# Rauchmelder_2_2.net
KiCad netlist of a schematic drawn in EAGLE
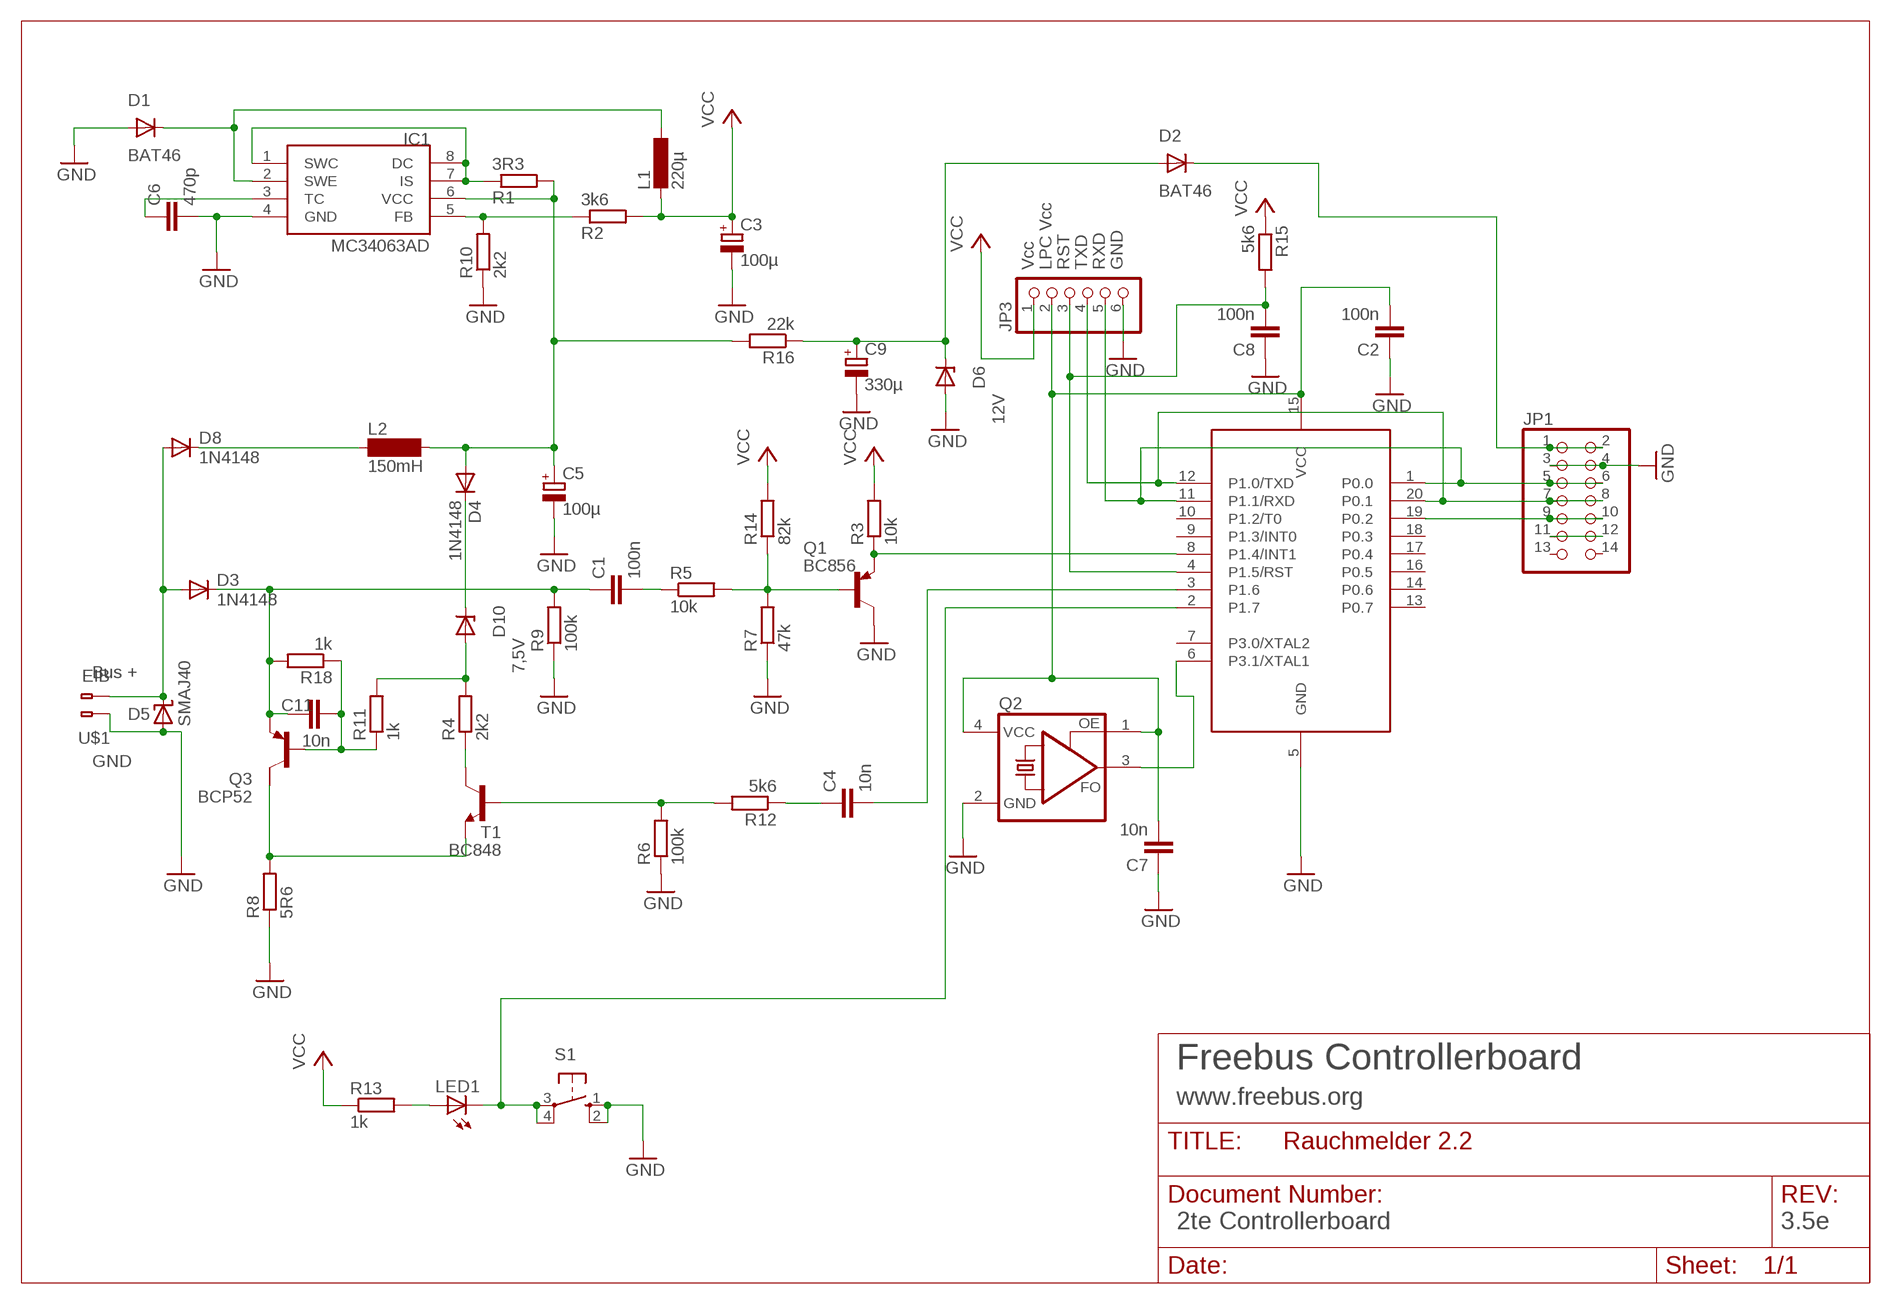
[diagram p0: schematic, sheet 1]

(export (version "E")
  (design (tool "Eeschema 10.0.6"))
  (components
    (comp (ref "C1")
      (value "100n")
      (footprint "eagle-import:C1206")
      (libsource (lib "eagle-import") (part "C-EUC1206"))
    )
    (comp (ref "C2")
      (value "100n")
      (footprint "eagle-import:C1206")
      (libsource (lib "eagle-import") (part "C-EUC1206"))
    )
    (comp (ref "C3")
      (value "100µ")
      (footprint "eagle-import:SANYO-OSCON_SMD_B6")
      (libsource (lib "eagle-import") (part "CPOL-EUSANYO_SMD_B6"))
    )
    (comp (ref "C4")
      (value "10n")
      (footprint "eagle-import:C1206")
      (libsource (lib "eagle-import") (part "C-EUC1206"))
    )
    (comp (ref "C5")
      (value "100µ")
      (footprint "eagle-import:SANYO-OSCON_SMD_C6")
      (libsource (lib "eagle-import") (part "CPOL-EUSANYO_SMD_C6"))
    )
    (comp (ref "C6")
      (value "470p")
      (footprint "eagle-import:C1206")
      (libsource (lib "eagle-import") (part "C-EUC1206"))
    )
    (comp (ref "C7")
      (value "10n")
      (footprint "eagle-import:C1206")
      (libsource (lib "eagle-import") (part "C-EUC1206"))
    )
    (comp (ref "C8")
      (value "100n")
      (footprint "eagle-import:C1206")
      (libsource (lib "eagle-import") (part "C-EUC1206"))
    )
    (comp (ref "C9")
      (value "330µ")
      (footprint "eagle-import:E3,5-8")
      (libsource (lib "eagle-import") (part "CPOL-EUE3.5-8"))
    )
    (comp (ref "C11")
      (value "10n")
      (footprint "eagle-import:C1206")
      (libsource (lib "eagle-import") (part "C-EUC1206"))
    )
    (comp (ref "D1")
      (value "BAT46")
      (footprint "eagle-import:MINIMELF")
      (libsource (lib "eagle-import") (part "DIODE-MINIMELF"))
    )
    (comp (ref "D2")
      (value "BAT46")
      (footprint "eagle-import:MINIMELF")
      (libsource (lib "eagle-import") (part "DIODE-MINIMELF"))
    )
    (comp (ref "D3")
      (value "1N4148")
      (footprint "eagle-import:MINIMELF")
      (libsource (lib "eagle-import") (part "DIODE-MINIMELF"))
    )
    (comp (ref "D4")
      (value "1N4148")
      (footprint "eagle-import:MINIMELF")
      (libsource (lib "eagle-import") (part "DIODE-MINIMELF"))
    )
    (comp (ref "D5")
      (value "SMAJ40")
      (footprint "eagle-import:SMBJ")
      (libsource (lib "eagle-import") (part "SUPPRESSOR-SMBJ"))
    )
    (comp (ref "D6")
      (value "12V")
      (footprint "eagle-import:MINIMELF")
      (libsource (lib "eagle-import") (part "ZPD"))
    )
    (comp (ref "D8")
      (value "1N4148")
      (footprint "eagle-import:MINIMELF")
      (libsource (lib "eagle-import") (part "DIODE-MINIMELF"))
    )
    (comp (ref "D10")
      (value "7,5V")
      (footprint "eagle-import:MINIMELF")
      (libsource (lib "eagle-import") (part "ZPD"))
    )
    (comp (ref "IC1")
      (value "MC34063AD")
      (footprint "eagle-import:SOIC8")
      (libsource (lib "eagle-import") (part "MC34063AD"))
    )
    (comp (ref "IC3")
      (value "LPC922FDH")
      (footprint "eagle-import:TSSOP20")
      (libsource (lib "eagle-import") (part "LPC922FDH"))
    )
    (comp (ref "JP1")
      (value "PINHD-2X7")
      (footprint "eagle-import:2X07")
      (libsource (lib "eagle-import") (part "PINHD-2X7"))
    )
    (comp (ref "JP3")
      (value "PINHD-1X6")
      (footprint "eagle-import:1X06")
      (libsource (lib "eagle-import") (part "PINHD-1X6"))
    )
    (comp (ref "L1")
      (value "220µ")
      (footprint "eagle-import:0207_12")
      (libsource (lib "eagle-import") (part "L-EU0207/12"))
    )
    (comp (ref "L2")
      (value "150mH")
      (footprint "eagle-import:BS11")
      (libsource (lib "eagle-import") (part "BS11"))
    )
    (comp (ref "LED1")
      (value "LED3MM")
      (footprint "eagle-import:LED3MM")
      (libsource (lib "eagle-import") (part "LED3MM"))
    )
    (comp (ref "Q1")
      (value "BC856")
      (footprint "eagle-import:SOT23-BEC")
      (libsource (lib "eagle-import") (part "BC856SMDALT1"))
    )
    (comp (ref "Q2")
      (value "ASFL")
      (footprint "eagle-import:ASF")
      (libsource (lib "eagle-import") (part "ASFL"))
    )
    (comp (ref "Q3")
      (value "BCP52")
      (footprint "eagle-import:SOT223")
      (libsource (lib "eagle-import") (part "FZT753SMD"))
    )
    (comp (ref "R1")
      (value "3R3")
      (footprint "eagle-import:R1206")
      (libsource (lib "eagle-import") (part "R-EU_R1206"))
    )
    (comp (ref "R2")
      (value "3k6")
      (footprint "eagle-import:R1206")
      (libsource (lib "eagle-import") (part "R-EU_R1206"))
    )
    (comp (ref "R3")
      (value "10k")
      (footprint "eagle-import:R1206")
      (libsource (lib "eagle-import") (part "R-EU_R1206"))
    )
    (comp (ref "R4")
      (value "2k2")
      (footprint "eagle-import:R1206")
      (libsource (lib "eagle-import") (part "R-EU_R1206"))
    )
    (comp (ref "R5")
      (value "10k")
      (footprint "eagle-import:R1206")
      (libsource (lib "eagle-import") (part "R-EU_R1206"))
    )
    (comp (ref "R6")
      (value "100k")
      (footprint "eagle-import:R1206")
      (libsource (lib "eagle-import") (part "R-EU_R1206"))
    )
    (comp (ref "R7")
      (value "47k")
      (footprint "eagle-import:R1206")
      (libsource (lib "eagle-import") (part "R-EU_R1206"))
    )
    (comp (ref "R8")
      (value "5R6")
      (footprint "eagle-import:R1206")
      (libsource (lib "eagle-import") (part "R-EU_R1206"))
    )
    (comp (ref "R9")
      (value "100k")
      (footprint "eagle-import:R1206")
      (libsource (lib "eagle-import") (part "R-EU_R1206"))
    )
    (comp (ref "R10")
      (value "2k2")
      (footprint "eagle-import:R1206")
      (libsource (lib "eagle-import") (part "R-EU_R1206"))
    )
    (comp (ref "R11")
      (value "1k")
      (footprint "eagle-import:R1206")
      (libsource (lib "eagle-import") (part "R-EU_R1206"))
    )
    (comp (ref "R12")
      (value "5k6")
      (footprint "eagle-import:R1206")
      (libsource (lib "eagle-import") (part "R-EU_R1206"))
    )
    (comp (ref "R13")
      (value "1k")
      (footprint "eagle-import:R1206")
      (libsource (lib "eagle-import") (part "R-EU_R1206"))
    )
    (comp (ref "R14")
      (value "82k")
      (footprint "eagle-import:R1206")
      (libsource (lib "eagle-import") (part "R-EU_R1206"))
    )
    (comp (ref "R15")
      (value "5k6")
      (footprint "eagle-import:R1206")
      (libsource (lib "eagle-import") (part "R-EU_R1206"))
    )
    (comp (ref "R16")
      (value "22k")
      (footprint "eagle-import:R1206")
      (libsource (lib "eagle-import") (part "R-EU_R1206"))
    )
    (comp (ref "R18")
      (value "1k")
      (footprint "eagle-import:R1206")
      (libsource (lib "eagle-import") (part "R-EU_R1206"))
    )
    (comp (ref "S1")
      (value "10-XX")
      (footprint "eagle-import:B3F-10XX")
      (libsource (lib "eagle-import") (part "10-XX"))
    )
    (comp (ref "T1")
      (value "BC848")
      (footprint "eagle-import:SOT23")
      (libsource (lib "eagle-import") (part "BC848"))
    )
    (comp (ref "U$1")
      (value "EIB")
      (footprint "eagle-import:BUSKLEMME243-724")
      (libsource (lib "eagle-import") (part "EIB"))
    )
  )
  (nets
    (net (code "1") (name "GND") (class "Default")
      (node (ref "C2") (pin "1") (pinfunction "1_1") (pintype "passive"))
      (node (ref "C3") (pin "-") (pinfunction "-_-") (pintype "passive"))
      (node (ref "C5") (pin "-") (pinfunction "-_-") (pintype "passive"))
      (node (ref "C6") (pin "2") (pinfunction "2_2") (pintype "passive"))
      (node (ref "C7") (pin "1") (pinfunction "1_1") (pintype "passive"))
      (node (ref "C8") (pin "1") (pinfunction "1_1") (pintype "passive"))
      (node (ref "C9") (pin "-") (pinfunction "-_-") (pintype "passive"))
      (node (ref "D1") (pin "A") (pinfunction "A_A") (pintype "passive"))
      (node (ref "D5") (pin "A") (pinfunction "A_A") (pintype "passive"))
      (node (ref "D6") (pin "A") (pinfunction "A_A") (pintype "passive"))
      (node (ref "IC1") (pin "4") (pinfunction "GND_4") (pintype "passive"))
      (node (ref "IC3") (pin "5") (pinfunction "GND_5") (pintype "bidirectional"))
      (node (ref "JP1") (pin "3") (pinfunction "3_3") (pintype "passive"))
      (node (ref "JP1") (pin "4") (pinfunction "4_4") (pintype "passive"))
      (node (ref "JP3") (pin "6") (pinfunction "6_6") (pintype "passive"))
      (node (ref "Q1") (pin "C") (pinfunction "C_C") (pintype "passive"))
      (node (ref "Q2") (pin "2") (pinfunction "GND_2") (pintype "power_in"))
      (node (ref "R10") (pin "1") (pinfunction "1_1") (pintype "passive"))
      (node (ref "R6") (pin "1") (pinfunction "1_1") (pintype "passive"))
      (node (ref "R7") (pin "1") (pinfunction "1_1") (pintype "passive"))
      (node (ref "R8") (pin "1") (pinfunction "1_1") (pintype "passive"))
      (node (ref "R9") (pin "1") (pinfunction "1_1") (pintype "passive"))
      (node (ref "S1") (pin "1") (pinfunction "S_1") (pintype "passive"))
      (node (ref "S1") (pin "2") (pinfunction "S1_2") (pintype "passive"))
      (node (ref "U$1") (pin "1") (pinfunction "B-1_1") (pintype "passive"))
    )
    (net (code "2") (name "Net-(C1-Pad2)") (class "Default")
      (node (ref "C1") (pin "2") (pinfunction "2_2") (pintype "passive"))
      (node (ref "R5") (pin "1") (pinfunction "1_1") (pintype "passive"))
    )
    (net (code "3") (name "Net-(C4-Pad1)") (class "Default")
      (node (ref "C4") (pin "1") (pinfunction "1_1") (pintype "passive"))
      (node (ref "R12") (pin "1") (pinfunction "1_1") (pintype "passive"))
    )
    (net (code "4") (name "Net-(C9-Pad+)") (class "Default")
      (node (ref "C9") (pin "+") (pinfunction "+_+") (pintype "passive"))
      (node (ref "D2") (pin "A") (pinfunction "A_A") (pintype "passive"))
      (node (ref "D6") (pin "C") (pinfunction "C_C") (pintype "passive"))
      (node (ref "R16") (pin "1") (pinfunction "1_1") (pintype "passive"))
    )
    (net (code "5") (name "Net-(D2-PadC)") (class "Default")
      (node (ref "D2") (pin "C") (pinfunction "C_C") (pintype "passive"))
      (node (ref "JP1") (pin "1") (pinfunction "1_1") (pintype "passive"))
      (node (ref "JP1") (pin "2") (pinfunction "2_2") (pintype "passive"))
    )
    (net (code "6") (name "Net-(D8-PadC)") (class "Default")
      (node (ref "D8") (pin "C") (pinfunction "C_C") (pintype "passive"))
      (node (ref "L2") (pin "1") (pinfunction "1_1") (pintype "passive"))
    )
    (net (code "7") (name "Net-(D10-PadA)") (class "Default")
      (node (ref "D10") (pin "A") (pinfunction "A_A") (pintype "passive"))
      (node (ref "R11") (pin "2") (pinfunction "2_2") (pintype "passive"))
      (node (ref "R4") (pin "2") (pinfunction "2_2") (pintype "passive"))
    )
    (net (code "8") (name "Net-(D10-PadC)") (class "Default")
      (node (ref "D10") (pin "C") (pinfunction "C_C") (pintype "passive"))
      (node (ref "D4") (pin "C") (pinfunction "C_C") (pintype "passive"))
    )
    (net (code "9") (name "Net-(IC1-DC)") (class "Default")
      (node (ref "IC1") (pin "1") (pinfunction "SWC_1") (pintype "passive"))
      (node (ref "IC1") (pin "7") (pinfunction "IS_7") (pintype "passive"))
      (node (ref "IC1") (pin "8") (pinfunction "DC_8") (pintype "passive"))
      (node (ref "R1") (pin "1") (pinfunction "1_1") (pintype "passive"))
    )
    (net (code "10") (name "Net-(IC1-FB)") (class "Default")
      (node (ref "IC1") (pin "5") (pinfunction "FB_5") (pintype "passive"))
      (node (ref "R10") (pin "2") (pinfunction "2_2") (pintype "passive"))
      (node (ref "R2") (pin "1") (pinfunction "1_1") (pintype "passive"))
    )
    (net (code "11") (name "Net-(IC1-SWE)") (class "Default")
      (node (ref "D1") (pin "C") (pinfunction "C_C") (pintype "passive"))
      (node (ref "IC1") (pin "2") (pinfunction "SWE_2") (pintype "passive"))
      (node (ref "L1") (pin "1") (pinfunction "1_1") (pintype "passive"))
    )
    (net (code "12") (name "Net-(IC1-TC)") (class "Default")
      (node (ref "C6") (pin "1") (pinfunction "1_1") (pintype "passive"))
      (node (ref "IC1") (pin "3") (pinfunction "TC_3") (pintype "passive"))
    )
    (net (code "13") (name "Net-(IC1-VCC)") (class "Default")
      (node (ref "C5") (pin "+") (pinfunction "+_+") (pintype "passive"))
      (node (ref "D4") (pin "A") (pinfunction "A_A") (pintype "passive"))
      (node (ref "IC1") (pin "6") (pinfunction "VCC_6") (pintype "passive"))
      (node (ref "L2") (pin "2") (pinfunction "2_2") (pintype "passive"))
      (node (ref "R1") (pin "2") (pinfunction "2_2") (pintype "passive"))
      (node (ref "R16") (pin "2") (pinfunction "2_2") (pintype "passive"))
    )
    (net (code "14") (name "Net-(IC3-P0.0)") (class "Default")
      (node (ref "IC3") (pin "1") (pinfunction "P0.0_1") (pintype "bidirectional"))
      (node (ref "IC3") (pin "11") (pinfunction "P1.1/RXD_11") (pintype "bidirectional"))
      (node (ref "JP1") (pin "5") (pinfunction "5_5") (pintype "passive"))
      (node (ref "JP1") (pin "6") (pinfunction "6_6") (pintype "passive"))
      (node (ref "JP3") (pin "5") (pinfunction "5_5") (pintype "passive"))
    )
    (net (code "15") (name "Net-(IC3-P0.1)") (class "Default")
      (node (ref "IC3") (pin "12") (pinfunction "P1.0/TXD_12") (pintype "bidirectional"))
      (node (ref "IC3") (pin "20") (pinfunction "P0.1_20") (pintype "bidirectional"))
      (node (ref "JP1") (pin "7") (pinfunction "7_7") (pintype "passive"))
      (node (ref "JP1") (pin "8") (pinfunction "8_8") (pintype "passive"))
      (node (ref "JP3") (pin "4") (pinfunction "4_4") (pintype "passive"))
    )
    (net (code "16") (name "Net-(IC3-P0.2)") (class "Default")
      (node (ref "IC3") (pin "19") (pinfunction "P0.2_19") (pintype "bidirectional"))
      (node (ref "JP1") (pin "10") (pinfunction "10_10") (pintype "passive"))
      (node (ref "JP1") (pin "9") (pinfunction "9_9") (pintype "passive"))
    )
    (net (code "17") (name "Net-(IC3-P1.4{slash}INT1)") (class "Default")
      (node (ref "IC3") (pin "8") (pinfunction "P1.4/INT1_8") (pintype "bidirectional"))
      (node (ref "Q1") (pin "E") (pinfunction "E_E") (pintype "passive"))
      (node (ref "R3") (pin "1") (pinfunction "1_1") (pintype "passive"))
    )
    (net (code "18") (name "Net-(IC3-P1.5{slash}RST)") (class "Default")
      (node (ref "C8") (pin "2") (pinfunction "2_2") (pintype "passive"))
      (node (ref "IC3") (pin "4") (pinfunction "P1.5/RST_4") (pintype "bidirectional"))
      (node (ref "JP3") (pin "3") (pinfunction "3_3") (pintype "passive"))
      (node (ref "R15") (pin "2") (pinfunction "2_2") (pintype "passive"))
    )
    (net (code "19") (name "Net-(IC3-P1.6)") (class "Default")
      (node (ref "C4") (pin "2") (pinfunction "2_2") (pintype "passive"))
      (node (ref "IC3") (pin "3") (pinfunction "P1.6_3") (pintype "bidirectional"))
    )
    (net (code "20") (name "Net-(IC3-P1.7)") (class "Default")
      (node (ref "IC3") (pin "2") (pinfunction "P1.7_2") (pintype "bidirectional"))
      (node (ref "LED1") (pin "K") (pinfunction "C_K") (pintype "passive"))
      (node (ref "S1") (pin "3") (pinfunction "P_3") (pintype "passive"))
      (node (ref "S1") (pin "4") (pinfunction "P1_4") (pintype "passive"))
    )
    (net (code "21") (name "Net-(IC3-P3.1{slash}XTAL1)") (class "Default")
      (node (ref "IC3") (pin "6") (pinfunction "P3.1/XTAL1_6") (pintype "bidirectional"))
      (node (ref "Q2") (pin "3") (pinfunction "FO_3") (pintype "output"))
    )
    (net (code "22") (name "Net-(IC3-VCC)") (class "Default")
      (node (ref "C2") (pin "2") (pinfunction "2_2") (pintype "passive"))
      (node (ref "C7") (pin "2") (pinfunction "2_2") (pintype "passive"))
      (node (ref "IC3") (pin "15") (pinfunction "VCC_15") (pintype "bidirectional"))
      (node (ref "JP3") (pin "2") (pinfunction "2_2") (pintype "passive"))
      (node (ref "Q2") (pin "1") (pinfunction "OE_1") (pintype "input"))
      (node (ref "Q2") (pin "4") (pinfunction "VCC_4") (pintype "power_in"))
    )
    (net (code "23") (name "Net-(JP1-Pad11)") (class "Default")
      (node (ref "JP1") (pin "11") (pinfunction "11_11") (pintype "passive"))
      (node (ref "JP1") (pin "12") (pinfunction "12_12") (pintype "passive"))
    )
    (net (code "24") (name "Net-(LED1-PadA)") (class "Default")
      (node (ref "LED1") (pin "A") (pinfunction "A_A") (pintype "passive"))
      (node (ref "R13") (pin "2") (pinfunction "2_2") (pintype "passive"))
    )
    (net (code "25") (name "Net-(Q1-PadB)") (class "Default")
      (node (ref "Q1") (pin "B") (pinfunction "B_B") (pintype "passive"))
      (node (ref "R14") (pin "1") (pinfunction "1_1") (pintype "passive"))
      (node (ref "R5") (pin "2") (pinfunction "2_2") (pintype "passive"))
      (node (ref "R7") (pin "2") (pinfunction "2_2") (pintype "passive"))
    )
    (net (code "26") (name "Net-(Q3-B)") (class "Default")
      (node (ref "C11") (pin "2") (pinfunction "2_2") (pintype "passive"))
      (node (ref "Q3") (pin "1") (pinfunction "B_1") (pintype "passive"))
      (node (ref "R11") (pin "1") (pinfunction "1_1") (pintype "passive"))
      (node (ref "R18") (pin "1") (pinfunction "1_1") (pintype "passive"))
    )
    (net (code "27") (name "Net-(Q3-C)") (class "Default")
      (node (ref "Q3") (pin "2") (pinfunction "C_2") (pintype "passive"))
      (node (ref "R8") (pin "2") (pinfunction "2_2") (pintype "passive"))
      (node (ref "T1") (pin "2") (pinfunction "E_2") (pintype "passive"))
    )
    (net (code "28") (name "Net-(Q3-E)") (class "Default")
      (node (ref "C1") (pin "1") (pinfunction "1_1") (pintype "passive"))
      (node (ref "C11") (pin "1") (pinfunction "1_1") (pintype "passive"))
      (node (ref "D3") (pin "C") (pinfunction "C_C") (pintype "passive"))
      (node (ref "Q3") (pin "3") (pinfunction "E_3") (pintype "passive"))
      (node (ref "R18") (pin "2") (pinfunction "2_2") (pintype "passive"))
      (node (ref "R9") (pin "2") (pinfunction "2_2") (pintype "passive"))
    )
    (net (code "29") (name "Net-(T1-B)") (class "Default")
      (node (ref "R12") (pin "2") (pinfunction "2_2") (pintype "passive"))
      (node (ref "R6") (pin "2") (pinfunction "2_2") (pintype "passive"))
      (node (ref "T1") (pin "1") (pinfunction "B_1") (pintype "passive"))
    )
    (net (code "30") (name "Net-(T1-C)") (class "Default")
      (node (ref "R4") (pin "1") (pinfunction "1_1") (pintype "passive"))
      (node (ref "T1") (pin "3") (pinfunction "C_3") (pintype "passive"))
    )
    (net (code "31") (name "Net-(U$1-B-2)") (class "Default")
      (node (ref "D3") (pin "A") (pinfunction "A_A") (pintype "passive"))
      (node (ref "D5") (pin "C") (pinfunction "C_C") (pintype "passive"))
      (node (ref "D8") (pin "A") (pinfunction "A_A") (pintype "passive"))
      (node (ref "U$1") (pin "2") (pinfunction "B-2_2") (pintype "passive"))
    )
    (net (code "32") (name "VCC") (class "Default")
      (node (ref "C3") (pin "+") (pinfunction "+_+") (pintype "passive"))
      (node (ref "JP3") (pin "1") (pinfunction "1_1") (pintype "passive"))
      (node (ref "L1") (pin "2") (pinfunction "2_2") (pintype "passive"))
      (node (ref "R13") (pin "1") (pinfunction "1_1") (pintype "passive"))
      (node (ref "R14") (pin "2") (pinfunction "2_2") (pintype "passive"))
      (node (ref "R15") (pin "1") (pinfunction "1_1") (pintype "passive"))
      (node (ref "R2") (pin "2") (pinfunction "2_2") (pintype "passive"))
      (node (ref "R3") (pin "2") (pinfunction "2_2") (pintype "passive"))
    )
    (net (code "33") (name "unconnected-(IC3-P0.3-Pad18)") (class "Default")
      (node (ref "IC3") (pin "18") (pinfunction "P0.3_18") (pintype "bidirectional"))
    )
    (net (code "34") (name "unconnected-(IC3-P0.4-Pad17)") (class "Default")
      (node (ref "IC3") (pin "17") (pinfunction "P0.4_17") (pintype "bidirectional"))
    )
    (net (code "35") (name "unconnected-(IC3-P0.5-Pad16)") (class "Default")
      (node (ref "IC3") (pin "16") (pinfunction "P0.5_16") (pintype "bidirectional"))
    )
    (net (code "36") (name "unconnected-(IC3-P0.6-Pad14)") (class "Default")
      (node (ref "IC3") (pin "14") (pinfunction "P0.6_14") (pintype "bidirectional"))
    )
    (net (code "37") (name "unconnected-(IC3-P0.7-Pad13)") (class "Default")
      (node (ref "IC3") (pin "13") (pinfunction "P0.7_13") (pintype "bidirectional"))
    )
    (net (code "38") (name "unconnected-(IC3-P1.2{slash}T0-Pad10)") (class "Default")
      (node (ref "IC3") (pin "10") (pinfunction "P1.2/T0_10") (pintype "bidirectional"))
    )
    (net (code "39") (name "unconnected-(IC3-P1.3{slash}INT0-Pad9)") (class "Default")
      (node (ref "IC3") (pin "9") (pinfunction "P1.3/INT0_9") (pintype "bidirectional"))
    )
    (net (code "40") (name "unconnected-(IC3-P3.0{slash}XTAL2-Pad7)") (class "Default")
      (node (ref "IC3") (pin "7") (pinfunction "P3.0/XTAL2_7") (pintype "bidirectional"))
    )
    (net (code "41") (name "unconnected-(JP1-Pad13)") (class "Default")
      (node (ref "JP1") (pin "13") (pinfunction "13_13") (pintype "passive"))
    )
    (net (code "42") (name "unconnected-(JP1-Pad14)") (class "Default")
      (node (ref "JP1") (pin "14") (pinfunction "14_14") (pintype "passive"))
    )
    (net (code "43") (name "unconnected-(Q3-C{slash}-Pad4)") (class "Default")
      (node (ref "Q3") (pin "4") (pinfunction "C/_4") (pintype "passive"))
    )
  )
)
